# nightlight_bjt.net
KiCad netlist of a schematic drawn in EAGLE
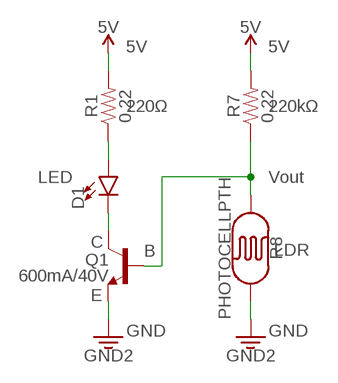
[diagram p0: schematic, sheet 1]

(export (version "E")
  (design (tool "Eeschema 10.0.6"))
  (components
    (comp (ref "D1")
      (value "LED5MM")
      (footprint "eagle-import:LED_5MM")
      (libsource (lib "eagle-import") (part "LED5MM"))
    )
    (comp (ref "Q1")
      (value "600mA/40V")
      (footprint "eagle-import:TO-92")
      (libsource (lib "eagle-import") (part "TRANS_NPN-P2N2222A"))
    )
    (comp (ref "R1")
      (value "0.22")
      (footprint "eagle-import:0805")
      (libsource (lib "eagle-import") (part "0.22OHM-0805-1/4W-1%"))
    )
    (comp (ref "R7")
      (value "0.22")
      (footprint "eagle-import:0805")
      (libsource (lib "eagle-import") (part "0.22OHM-0805-1/4W-1%"))
    )
    (comp (ref "R8")
      (value "PHOTOCELLPTH")
      (footprint "eagle-import:PHOTOCELL")
      (libsource (lib "eagle-import") (part "PHOTOCELLPTH"))
    )
  )
  (nets
    (net (code "1") (name "5V") (class "Default")
      (node (ref "R1") (pin "2") (pinfunction "2_2") (pintype "passive"))
      (node (ref "R7") (pin "2") (pinfunction "2_2") (pintype "passive"))
    )
    (net (code "2") (name "GND2") (class "Default")
      (node (ref "Q1") (pin "3") (pinfunction "E_3") (pintype "passive"))
      (node (ref "R8") (pin "2") (pinfunction "P$2_2") (pintype "bidirectional"))
    )
    (net (code "3") (name "Net-(D1-C)") (class "Default")
      (node (ref "D1") (pin "K") (pinfunction "C_K") (pintype "passive"))
      (node (ref "Q1") (pin "1") (pinfunction "C_1") (pintype "passive"))
    )
    (net (code "4") (name "Net-(D1-PadA)") (class "Default")
      (node (ref "D1") (pin "A") (pinfunction "A_A") (pintype "passive"))
      (node (ref "R1") (pin "1") (pinfunction "1_1") (pintype "passive"))
    )
    (net (code "5") (name "Net-(Q1-B)") (class "Default")
      (node (ref "Q1") (pin "2") (pinfunction "B_2") (pintype "passive"))
      (node (ref "R7") (pin "1") (pinfunction "1_1") (pintype "passive"))
      (node (ref "R8") (pin "1") (pinfunction "P$1_1") (pintype "bidirectional"))
    )
  )
)
